# SwitchNode.net
KiCad netlist of a schematic drawn in EAGLE
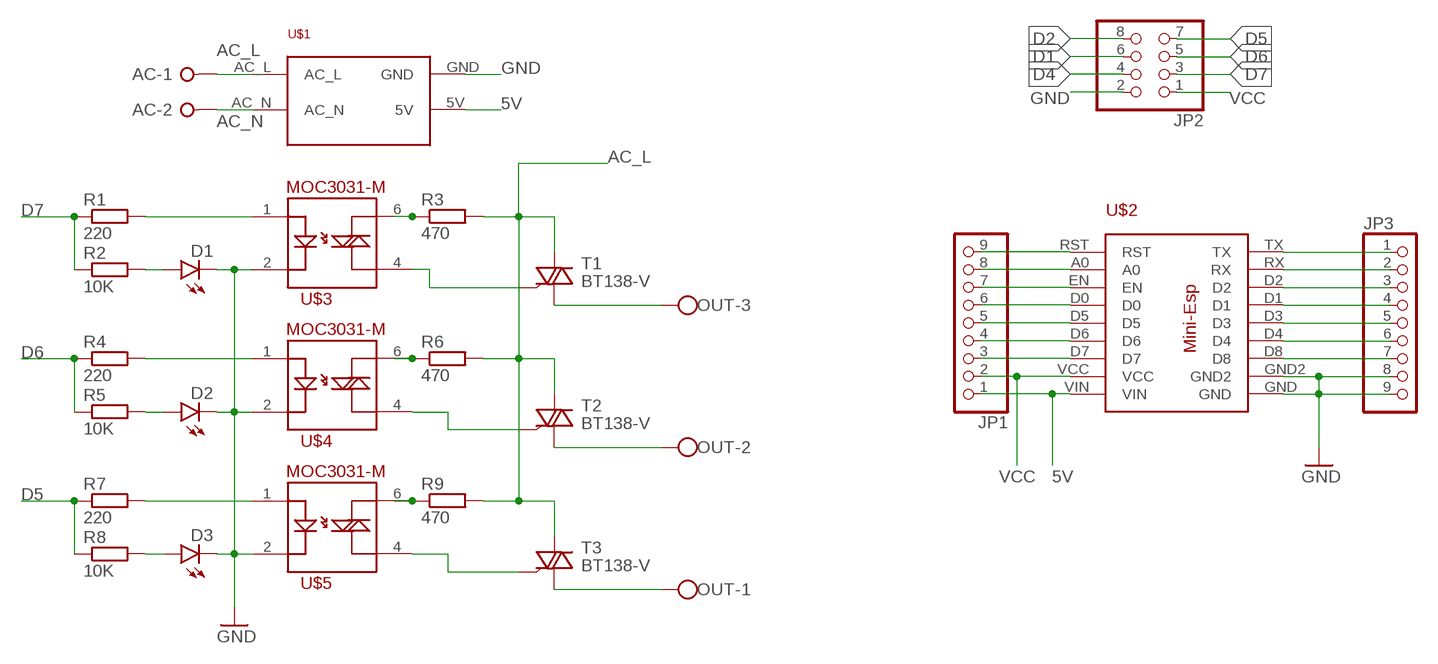
[diagram p0: schematic, sheet 1]

(export (version "E")
  (design (tool "Eeschema 10.0.6"))
  (components
    (comp (ref "AC")
      (value "W237-02P")
      (footprint "eagle-import:W237-132")
      (libsource (lib "eagle-import") (part "W237-02P"))
    )
    (comp (ref "D1")
      (value "LED3MM")
      (footprint "eagle-import:LED3MM")
      (libsource (lib "eagle-import") (part "LED3MM"))
    )
    (comp (ref "D2")
      (value "LED3MM")
      (footprint "eagle-import:LED3MM")
      (libsource (lib "eagle-import") (part "LED3MM"))
    )
    (comp (ref "D3")
      (value "LED3MM")
      (footprint "eagle-import:LED3MM")
      (libsource (lib "eagle-import") (part "LED3MM"))
    )
    (comp (ref "JP1")
      (value "PINHD-1X9")
      (footprint "eagle-import:1X09-BIG")
      (libsource (lib "eagle-import") (part "PINHD-1X9"))
    )
    (comp (ref "JP2")
      (value "PINHD-2X4")
      (footprint "eagle-import:2X04")
      (libsource (lib "eagle-import") (part "PINHD-2X4"))
    )
    (comp (ref "JP3")
      (value "PINHD-1X9")
      (footprint "eagle-import:1X09-BIG")
      (libsource (lib "eagle-import") (part "PINHD-1X9"))
    )
    (comp (ref "OUT")
      (value "W237-103")
      (footprint "eagle-import:W237-103")
      (fields (field (name "MPN") "237-103"))
      (libsource (lib "eagle-import") (part "W237-103"))
    )
    (comp (ref "R1")
      (value "220")
      (footprint "eagle-import:R0805")
      (libsource (lib "eagle-import") (part "R-EU_R0805"))
    )
    (comp (ref "R2")
      (value "10K")
      (footprint "eagle-import:R0805")
      (libsource (lib "eagle-import") (part "R-EU_R0805"))
    )
    (comp (ref "R3")
      (value "470")
      (footprint "eagle-import:R0805")
      (libsource (lib "eagle-import") (part "R-EU_R0805"))
    )
    (comp (ref "R4")
      (value "220")
      (footprint "eagle-import:R0805")
      (libsource (lib "eagle-import") (part "R-EU_R0805"))
    )
    (comp (ref "R5")
      (value "10K")
      (footprint "eagle-import:R0805")
      (libsource (lib "eagle-import") (part "R-EU_R0805"))
    )
    (comp (ref "R6")
      (value "470")
      (footprint "eagle-import:R0805")
      (libsource (lib "eagle-import") (part "R-EU_R0805"))
    )
    (comp (ref "R7")
      (value "220")
      (footprint "eagle-import:R0805")
      (libsource (lib "eagle-import") (part "R-EU_R0805"))
    )
    (comp (ref "R8")
      (value "10K")
      (footprint "eagle-import:R0805")
      (libsource (lib "eagle-import") (part "R-EU_R0805"))
    )
    (comp (ref "R9")
      (value "470")
      (footprint "eagle-import:R0805")
      (libsource (lib "eagle-import") (part "R-EU_R0805"))
    )
    (comp (ref "T1")
      (value "BT138-V")
      (footprint "eagle-import:TO220BV")
      (libsource (lib "eagle-import") (part "BT138-V"))
    )
    (comp (ref "T2")
      (value "BT138-V")
      (footprint "eagle-import:TO220BV")
      (libsource (lib "eagle-import") (part "BT138-V"))
    )
    (comp (ref "T3")
      (value "BT138-V")
      (footprint "eagle-import:TO220BV")
      (libsource (lib "eagle-import") (part "BT138-V"))
    )
    (comp (ref "U$1")
      (value "POWER_SUPPLY_220VAC_5V")
      (footprint "eagle-import:POWER_SUPPLY_220VAC_5V")
      (libsource (lib "eagle-import") (part "POWER_SUPPLY_220VAC_5V"))
    )
    (comp (ref "U$2")
      (value "MINI-ESP")
      (footprint "eagle-import:MINI-ESP")
      (libsource (lib "eagle-import") (part "MINI-ESP"))
    )
    (comp (ref "U$3")
      (value "MOC3031-M")
      (footprint "eagle-import:DIL06")
      (libsource (lib "eagle-import") (part "MOC3031-M"))
    )
    (comp (ref "U$4")
      (value "MOC3031-M")
      (footprint "eagle-import:DIL06")
      (libsource (lib "eagle-import") (part "MOC3031-M"))
    )
    (comp (ref "U$5")
      (value "MOC3031-M")
      (footprint "eagle-import:DIL06")
      (libsource (lib "eagle-import") (part "MOC3031-M"))
    )
  )
  (nets
    (net (code "1") (name "/5V") (class "Default")
      (node (ref "JP1") (pin "1") (pinfunction "1_1") (pintype "passive"))
      (node (ref "U$1") (pin "5V") (pinfunction "5V_5V") (pintype "bidirectional"))
      (node (ref "U$2") (pin "VIN") (pinfunction "VIN_VIN") (pintype "bidirectional"))
    )
    (net (code "2") (name "/AC_L") (class "Default")
      (node (ref "AC") (pin "1") (pinfunction "KL_1") (pintype "passive"))
      (node (ref "R3") (pin "2") (pinfunction "2_2") (pintype "passive"))
      (node (ref "R6") (pin "2") (pinfunction "2_2") (pintype "passive"))
      (node (ref "R9") (pin "2") (pinfunction "2_2") (pintype "passive"))
      (node (ref "T1") (pin "T2") (pinfunction "A2_T2") (pintype "passive"))
      (node (ref "T2") (pin "T2") (pinfunction "A2_T2") (pintype "passive"))
      (node (ref "T3") (pin "T2") (pinfunction "A2_T2") (pintype "passive"))
      (node (ref "U$1") (pin "AC_L") (pinfunction "AC_L_AC_L") (pintype "bidirectional"))
    )
    (net (code "3") (name "/AC_N") (class "Default")
      (node (ref "AC") (pin "2") (pinfunction "KL_2") (pintype "passive"))
      (node (ref "U$1") (pin "AC_N") (pinfunction "AC_N_AC_N") (pintype "bidirectional"))
    )
    (net (code "4") (name "/VCC") (class "Default")
      (node (ref "JP1") (pin "2") (pinfunction "2_2") (pintype "passive"))
      (node (ref "JP2") (pin "1") (pinfunction "1_1") (pintype "passive"))
      (node (ref "U$2") (pin "VCC") (pinfunction "VCC_VCC") (pintype "bidirectional"))
    )
    (net (code "5") (name "D1") (class "Default")
      (node (ref "JP2") (pin "6") (pinfunction "6_6") (pintype "passive"))
      (node (ref "JP3") (pin "4") (pinfunction "4_4") (pintype "passive"))
      (node (ref "U$2") (pin "D1") (pinfunction "D1_D1") (pintype "bidirectional"))
    )
    (net (code "6") (name "D2") (class "Default")
      (node (ref "JP2") (pin "8") (pinfunction "8_8") (pintype "passive"))
      (node (ref "JP3") (pin "3") (pinfunction "3_3") (pintype "passive"))
      (node (ref "U$2") (pin "D2") (pinfunction "D2_D2") (pintype "bidirectional"))
    )
    (net (code "7") (name "D4") (class "Default")
      (node (ref "JP2") (pin "4") (pinfunction "4_4") (pintype "passive"))
      (node (ref "JP3") (pin "6") (pinfunction "6_6") (pintype "passive"))
      (node (ref "U$2") (pin "D4") (pinfunction "D4_D4") (pintype "bidirectional"))
    )
    (net (code "8") (name "D5") (class "Default")
      (node (ref "JP1") (pin "5") (pinfunction "5_5") (pintype "passive"))
      (node (ref "JP2") (pin "7") (pinfunction "7_7") (pintype "passive"))
      (node (ref "R7") (pin "1") (pinfunction "1_1") (pintype "passive"))
      (node (ref "R8") (pin "1") (pinfunction "1_1") (pintype "passive"))
      (node (ref "U$2") (pin "D5") (pinfunction "D5_D5") (pintype "bidirectional"))
    )
    (net (code "9") (name "D6") (class "Default")
      (node (ref "JP1") (pin "4") (pinfunction "4_4") (pintype "passive"))
      (node (ref "JP2") (pin "5") (pinfunction "5_5") (pintype "passive"))
      (node (ref "R4") (pin "1") (pinfunction "1_1") (pintype "passive"))
      (node (ref "R5") (pin "1") (pinfunction "1_1") (pintype "passive"))
      (node (ref "U$2") (pin "D6") (pinfunction "D6_D6") (pintype "bidirectional"))
    )
    (net (code "10") (name "D7") (class "Default")
      (node (ref "JP1") (pin "3") (pinfunction "3_3") (pintype "passive"))
      (node (ref "JP2") (pin "3") (pinfunction "3_3") (pintype "passive"))
      (node (ref "R1") (pin "1") (pinfunction "1_1") (pintype "passive"))
      (node (ref "R2") (pin "1") (pinfunction "1_1") (pintype "passive"))
      (node (ref "U$2") (pin "D7") (pinfunction "D7_D7") (pintype "bidirectional"))
    )
    (net (code "11") (name "GND") (class "Default")
      (node (ref "D1") (pin "K") (pinfunction "C_K") (pintype "passive"))
      (node (ref "D2") (pin "K") (pinfunction "C_K") (pintype "passive"))
      (node (ref "D3") (pin "K") (pinfunction "C_K") (pintype "passive"))
      (node (ref "JP2") (pin "2") (pinfunction "2_2") (pintype "passive"))
      (node (ref "JP3") (pin "8") (pinfunction "8_8") (pintype "passive"))
      (node (ref "JP3") (pin "9") (pinfunction "9_9") (pintype "passive"))
      (node (ref "U$1") (pin "GND") (pinfunction "GND_GND") (pintype "bidirectional"))
      (node (ref "U$2") (pin "GND") (pinfunction "GND_GND") (pintype "bidirectional"))
      (node (ref "U$2") (pin "GND2") (pinfunction "GND2_GND2") (pintype "bidirectional"))
      (node (ref "U$3") (pin "2") (pinfunction "2_2") (pintype "bidirectional"))
      (node (ref "U$4") (pin "2") (pinfunction "2_2") (pintype "bidirectional"))
      (node (ref "U$5") (pin "2") (pinfunction "2_2") (pintype "bidirectional"))
    )
    (net (code "12") (name "Net-(D1-PadA)") (class "Default")
      (node (ref "D1") (pin "A") (pinfunction "A_A") (pintype "passive"))
      (node (ref "R2") (pin "2") (pinfunction "2_2") (pintype "passive"))
    )
    (net (code "13") (name "Net-(D2-PadA)") (class "Default")
      (node (ref "D2") (pin "A") (pinfunction "A_A") (pintype "passive"))
      (node (ref "R5") (pin "2") (pinfunction "2_2") (pintype "passive"))
    )
    (net (code "14") (name "Net-(D3-PadA)") (class "Default")
      (node (ref "D3") (pin "A") (pinfunction "A_A") (pintype "passive"))
      (node (ref "R8") (pin "2") (pinfunction "2_2") (pintype "passive"))
    )
    (net (code "15") (name "Net-(JP1-Pad6)") (class "Default")
      (node (ref "JP1") (pin "6") (pinfunction "6_6") (pintype "passive"))
      (node (ref "U$2") (pin "D0") (pinfunction "D0_D0") (pintype "bidirectional"))
    )
    (net (code "16") (name "Net-(JP1-Pad7)") (class "Default")
      (node (ref "JP1") (pin "7") (pinfunction "7_7") (pintype "passive"))
      (node (ref "U$2") (pin "EN") (pinfunction "EN_EN") (pintype "bidirectional"))
    )
    (net (code "17") (name "Net-(JP1-Pad8)") (class "Default")
      (node (ref "JP1") (pin "8") (pinfunction "8_8") (pintype "passive"))
      (node (ref "U$2") (pin "A0") (pinfunction "A0_A0") (pintype "bidirectional"))
    )
    (net (code "18") (name "Net-(JP1-Pad9)") (class "Default")
      (node (ref "JP1") (pin "9") (pinfunction "9_9") (pintype "passive"))
      (node (ref "U$2") (pin "RST") (pinfunction "RST_RST") (pintype "bidirectional"))
    )
    (net (code "19") (name "Net-(JP3-Pad1)") (class "Default")
      (node (ref "JP3") (pin "1") (pinfunction "1_1") (pintype "passive"))
      (node (ref "U$2") (pin "TX") (pinfunction "TX_TX") (pintype "bidirectional"))
    )
    (net (code "20") (name "Net-(JP3-Pad2)") (class "Default")
      (node (ref "JP3") (pin "2") (pinfunction "2_2") (pintype "passive"))
      (node (ref "U$2") (pin "RX") (pinfunction "RX_RX") (pintype "bidirectional"))
    )
    (net (code "21") (name "Net-(JP3-Pad5)") (class "Default")
      (node (ref "JP3") (pin "5") (pinfunction "5_5") (pintype "passive"))
      (node (ref "U$2") (pin "D3") (pinfunction "D3_D3") (pintype "bidirectional"))
    )
    (net (code "22") (name "Net-(JP3-Pad7)") (class "Default")
      (node (ref "JP3") (pin "7") (pinfunction "7_7") (pintype "passive"))
      (node (ref "U$2") (pin "D8") (pinfunction "D8_D8") (pintype "bidirectional"))
    )
    (net (code "23") (name "Net-(OUTA-KL)") (class "Default")
      (node (ref "OUT") (pin "1") (pinfunction "KL_1") (pintype "passive"))
      (node (ref "T3") (pin "T1") (pinfunction "A1_T1") (pintype "passive"))
    )
    (net (code "24") (name "Net-(OUTB-KL)") (class "Default")
      (node (ref "OUT") (pin "2") (pinfunction "KL_2") (pintype "passive"))
      (node (ref "T2") (pin "T1") (pinfunction "A1_T1") (pintype "passive"))
    )
    (net (code "25") (name "Net-(OUTC-KL)") (class "Default")
      (node (ref "OUT") (pin "3") (pinfunction "KL_3") (pintype "passive"))
      (node (ref "T1") (pin "T1") (pinfunction "A1_T1") (pintype "passive"))
    )
    (net (code "26") (name "Net-(R1-Pad2)") (class "Default")
      (node (ref "R1") (pin "2") (pinfunction "2_2") (pintype "passive"))
      (node (ref "U$3") (pin "1") (pinfunction "1_1") (pintype "bidirectional"))
    )
    (net (code "27") (name "Net-(R3-Pad1)") (class "Default")
      (node (ref "R3") (pin "1") (pinfunction "1_1") (pintype "passive"))
      (node (ref "U$3") (pin "6") (pinfunction "6_6") (pintype "bidirectional"))
    )
    (net (code "28") (name "Net-(R4-Pad2)") (class "Default")
      (node (ref "R4") (pin "2") (pinfunction "2_2") (pintype "passive"))
      (node (ref "U$4") (pin "1") (pinfunction "1_1") (pintype "bidirectional"))
    )
    (net (code "29") (name "Net-(R6-Pad1)") (class "Default")
      (node (ref "R6") (pin "1") (pinfunction "1_1") (pintype "passive"))
      (node (ref "U$4") (pin "6") (pinfunction "6_6") (pintype "bidirectional"))
    )
    (net (code "30") (name "Net-(R7-Pad2)") (class "Default")
      (node (ref "R7") (pin "2") (pinfunction "2_2") (pintype "passive"))
      (node (ref "U$5") (pin "1") (pinfunction "1_1") (pintype "bidirectional"))
    )
    (net (code "31") (name "Net-(R9-Pad1)") (class "Default")
      (node (ref "R9") (pin "1") (pinfunction "1_1") (pintype "passive"))
      (node (ref "U$5") (pin "6") (pinfunction "6_6") (pintype "bidirectional"))
    )
    (net (code "32") (name "Net-(T1-PadG)") (class "Default")
      (node (ref "T1") (pin "G") (pinfunction "G_G") (pintype "passive"))
      (node (ref "U$3") (pin "4") (pinfunction "4_4") (pintype "bidirectional"))
    )
    (net (code "33") (name "Net-(T2-PadG)") (class "Default")
      (node (ref "T2") (pin "G") (pinfunction "G_G") (pintype "passive"))
      (node (ref "U$4") (pin "4") (pinfunction "4_4") (pintype "bidirectional"))
    )
    (net (code "34") (name "Net-(T3-PadG)") (class "Default")
      (node (ref "T3") (pin "G") (pinfunction "G_G") (pintype "passive"))
      (node (ref "U$5") (pin "4") (pinfunction "4_4") (pintype "bidirectional"))
    )
  )
)
